# WizFi250_EVB_SCH_V100.net
KiCad netlist of a schematic drawn in EAGLE
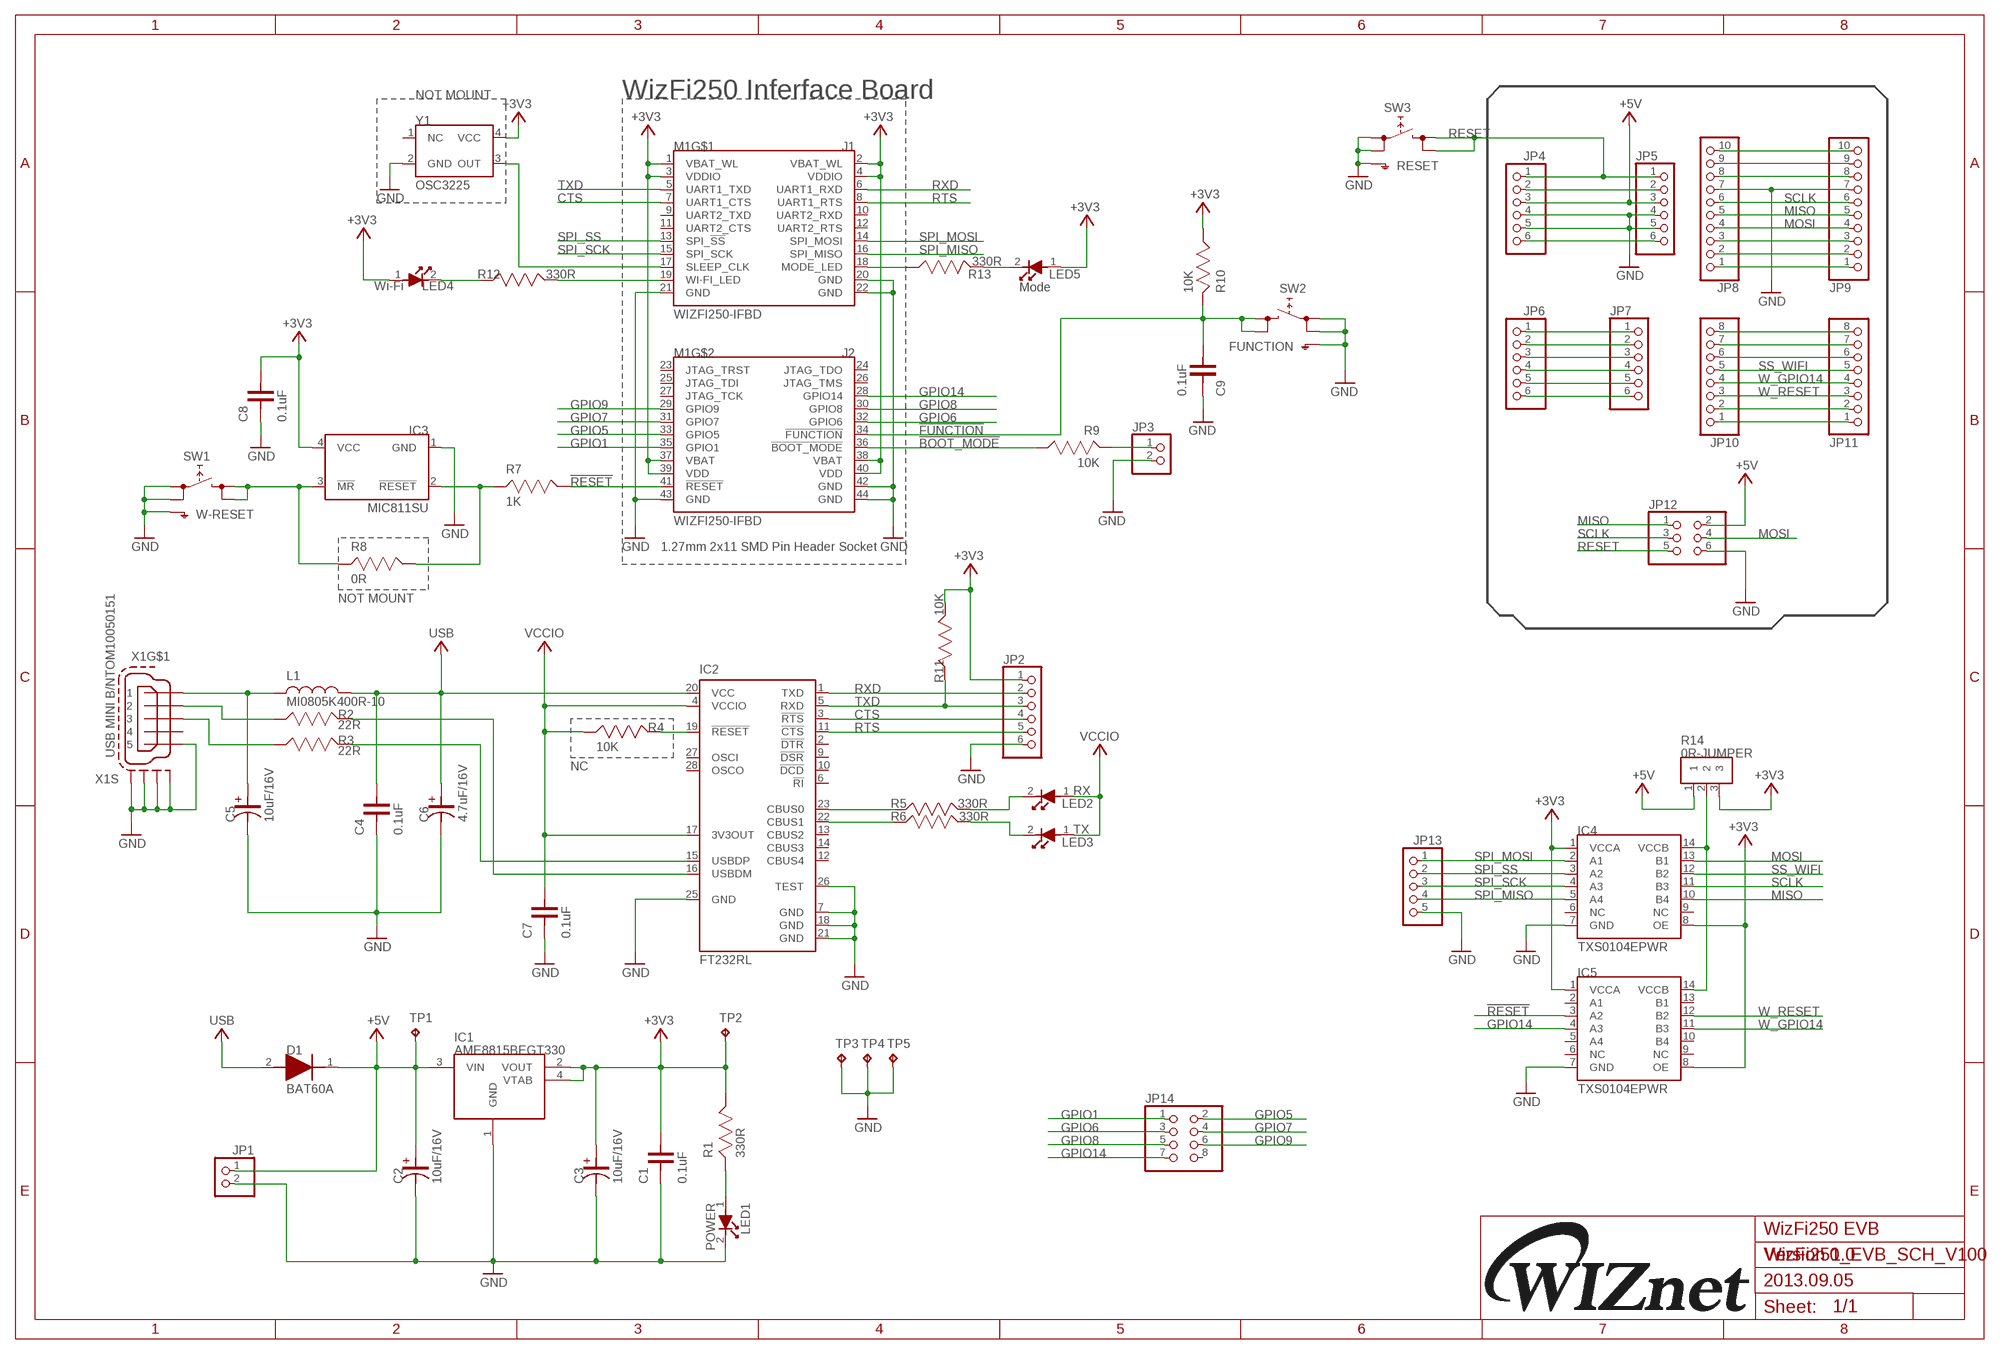
[diagram p0: schematic, sheet 1]

(export (version "E")
  (design (tool "Eeschema 10.0.6"))
  (components
    (comp (ref "C1")
      (value "0.1uF")
      (footprint "eagle-import:C-1608")
      (libsource (lib "eagle-import") (part "C-1608"))
    )
    (comp (ref "C2")
      (value "10uF/16V")
      (footprint "eagle-import:C-3216(TANTAL)")
      (libsource (lib "eagle-import") (part "C-3216(TANTAL)"))
    )
    (comp (ref "C3")
      (value "10uF/16V")
      (footprint "eagle-import:C-3216(TANTAL)")
      (libsource (lib "eagle-import") (part "C-3216(TANTAL)"))
    )
    (comp (ref "C4")
      (value "0.1uF")
      (footprint "eagle-import:C-1608")
      (libsource (lib "eagle-import") (part "C-1608"))
    )
    (comp (ref "C5")
      (value "10uF/16V")
      (footprint "eagle-import:C-3216(TANTAL)")
      (libsource (lib "eagle-import") (part "C-3216(TANTAL)"))
    )
    (comp (ref "C6")
      (value "4.7uF/16V")
      (footprint "eagle-import:C-3216(TANTAL)")
      (libsource (lib "eagle-import") (part "C-3216(TANTAL)"))
    )
    (comp (ref "C7")
      (value "0.1uF")
      (footprint "eagle-import:C-1608")
      (libsource (lib "eagle-import") (part "C-1608"))
    )
    (comp (ref "C8")
      (value "0.1uF")
      (footprint "eagle-import:C-1608")
      (libsource (lib "eagle-import") (part "C-1608"))
    )
    (comp (ref "C9")
      (value "0.1uF")
      (footprint "eagle-import:C-1608")
      (libsource (lib "eagle-import") (part "C-1608"))
    )
    (comp (ref "D1")
      (value "BAT60A")
      (footprint "eagle-import:BAT60A")
      (libsource (lib "eagle-import") (part "BAT60A"))
    )
    (comp (ref "IC1")
      (value "AME8815BEGT330")
      (footprint "eagle-import:SOT-223")
      (libsource (lib "eagle-import") (part "AME8815BEGT330"))
    )
    (comp (ref "IC2")
      (value "FT232RL")
      (footprint "eagle-import:SSOP28")
      (libsource (lib "eagle-import") (part "FT232RL"))
    )
    (comp (ref "IC3")
      (value "MIC811SU")
      (footprint "eagle-import:MIC811SU")
      (libsource (lib "eagle-import") (part "MIC811SU"))
    )
    (comp (ref "IC4")
      (value "TXS0104EPWR")
      (footprint "eagle-import:TXS0104EPWR")
      (libsource (lib "eagle-import") (part "TXS0104EPWR"))
    )
    (comp (ref "IC5")
      (value "TXS0104EPWR")
      (footprint "eagle-import:TXS0104EPWR")
      (libsource (lib "eagle-import") (part "TXS0104EPWR"))
    )
    (comp (ref "JP1")
      (value "PINHD-1X2")
      (footprint "eagle-import:1X02")
      (libsource (lib "eagle-import") (part "PINHD-1X2"))
    )
    (comp (ref "JP2")
      (value "PINHD-1X6")
      (footprint "eagle-import:1X06")
      (libsource (lib "eagle-import") (part "PINHD-1X6"))
    )
    (comp (ref "JP3")
      (value "PINHD-1X2")
      (footprint "eagle-import:1X02")
      (libsource (lib "eagle-import") (part "PINHD-1X2"))
    )
    (comp (ref "JP4")
      (value "PINHD-1X6")
      (footprint "eagle-import:1X06")
      (libsource (lib "eagle-import") (part "PINHD-1X6"))
    )
    (comp (ref "JP5")
      (value "PINHD-1X6")
      (footprint "eagle-import:1X06")
      (libsource (lib "eagle-import") (part "PINHD-1X6"))
    )
    (comp (ref "JP6")
      (value "PINHD-1X6")
      (footprint "eagle-import:1X06")
      (libsource (lib "eagle-import") (part "PINHD-1X6"))
    )
    (comp (ref "JP7")
      (value "PINHD-1X6")
      (footprint "eagle-import:1X06")
      (libsource (lib "eagle-import") (part "PINHD-1X6"))
    )
    (comp (ref "JP8")
      (value "PINHD-1X10")
      (footprint "eagle-import:1X10")
      (libsource (lib "eagle-import") (part "PINHD-1X10"))
    )
    (comp (ref "JP9")
      (value "PINHD-1X10")
      (footprint "eagle-import:1X10")
      (libsource (lib "eagle-import") (part "PINHD-1X10"))
    )
    (comp (ref "JP10")
      (value "PINHD-1X8")
      (footprint "eagle-import:1X08")
      (libsource (lib "eagle-import") (part "PINHD-1X8"))
    )
    (comp (ref "JP11")
      (value "PINHD-1X8")
      (footprint "eagle-import:1X08")
      (libsource (lib "eagle-import") (part "PINHD-1X8"))
    )
    (comp (ref "JP12")
      (value "PINHD-2X3")
      (footprint "eagle-import:2X03")
      (libsource (lib "eagle-import") (part "PINHD-2X3"))
    )
    (comp (ref "JP13")
      (value "PINHD-1X5")
      (footprint "eagle-import:1X05")
      (libsource (lib "eagle-import") (part "PINHD-1X5"))
    )
    (comp (ref "JP14")
      (value "PINHD-2X4")
      (footprint "eagle-import:2X04")
      (libsource (lib "eagle-import") (part "PINHD-2X4"))
    )
    (comp (ref "L1")
      (value "MI0805K400R-10")
      (footprint "eagle-import:L-2012")
      (libsource (lib "eagle-import") (part "L-2012"))
    )
    (comp (ref "LED1")
      (value "POWER")
      (footprint "eagle-import:LED-1608")
      (libsource (lib "eagle-import") (part "LED-1608"))
    )
    (comp (ref "LED2")
      (value "RX")
      (footprint "eagle-import:LED-1608")
      (libsource (lib "eagle-import") (part "LED-1608"))
    )
    (comp (ref "LED3")
      (value "TX")
      (footprint "eagle-import:LED-1608")
      (libsource (lib "eagle-import") (part "LED-1608"))
    )
    (comp (ref "LED4")
      (value "Wi-Fi")
      (footprint "eagle-import:LED-1608")
      (libsource (lib "eagle-import") (part "LED-1608"))
    )
    (comp (ref "LED5")
      (value "Mode")
      (footprint "eagle-import:LED-1608")
      (libsource (lib "eagle-import") (part "LED-1608"))
    )
    (comp (ref "M1")
      (value "WIZFI250-IFBD")
      (footprint "eagle-import:WIZFI250-IFBD")
      (libsource (lib "eagle-import") (part "WIZFI250-IFBD"))
    )
    (comp (ref "R1")
      (value "330R")
      (footprint "eagle-import:R-1608")
      (libsource (lib "eagle-import") (part "R-1608"))
    )
    (comp (ref "R2")
      (value "22R")
      (footprint "eagle-import:R-1608")
      (libsource (lib "eagle-import") (part "R-1608"))
    )
    (comp (ref "R3")
      (value "22R")
      (footprint "eagle-import:R-1608")
      (libsource (lib "eagle-import") (part "R-1608"))
    )
    (comp (ref "R4")
      (value "10K")
      (footprint "eagle-import:R-1608")
      (libsource (lib "eagle-import") (part "R-1608"))
    )
    (comp (ref "R5")
      (value "330R")
      (footprint "eagle-import:R-1608")
      (libsource (lib "eagle-import") (part "R-1608"))
    )
    (comp (ref "R6")
      (value "330R")
      (footprint "eagle-import:R-1608")
      (libsource (lib "eagle-import") (part "R-1608"))
    )
    (comp (ref "R7")
      (value "1K")
      (footprint "eagle-import:R-1608")
      (libsource (lib "eagle-import") (part "R-1608"))
    )
    (comp (ref "R8")
      (value "0R")
      (footprint "eagle-import:R-1608")
      (libsource (lib "eagle-import") (part "R-1608"))
    )
    (comp (ref "R9")
      (value "10K")
      (footprint "eagle-import:R-1608")
      (libsource (lib "eagle-import") (part "R-1608"))
    )
    (comp (ref "R10")
      (value "10K")
      (footprint "eagle-import:R-1608")
      (libsource (lib "eagle-import") (part "R-1608"))
    )
    (comp (ref "R11")
      (value "10K")
      (footprint "eagle-import:R-1608")
      (libsource (lib "eagle-import") (part "R-1608"))
    )
    (comp (ref "R12")
      (value "330R")
      (footprint "eagle-import:R-1608")
      (libsource (lib "eagle-import") (part "R-1608"))
    )
    (comp (ref "R13")
      (value "330R")
      (footprint "eagle-import:R-1608")
      (libsource (lib "eagle-import") (part "R-1608"))
    )
    (comp (ref "R14")
      (value "0R-JUMPER")
      (footprint "eagle-import:R-1608-JUMPER")
      (libsource (lib "eagle-import") (part "R-1608-JUMPER"))
    )
    (comp (ref "SW1")
      (value "W-RESET")
      (footprint "eagle-import:SKHMPXE010")
      (libsource (lib "eagle-import") (part "SKHMPE010S"))
    )
    (comp (ref "SW2")
      (value "FUNCTION")
      (footprint "eagle-import:SKHMPXE010")
      (libsource (lib "eagle-import") (part "SKHMPE010S"))
    )
    (comp (ref "SW3")
      (value "RESET")
      (footprint "eagle-import:SKHMPXE010")
      (libsource (lib "eagle-import") (part "SKHMPE010S"))
    )
    (comp (ref "TP1")
      (value "TPB1,27")
      (footprint "eagle-import:B1,27")
      (libsource (lib "eagle-import") (part "TPB1,27"))
    )
    (comp (ref "TP2")
      (value "TPB1,27")
      (footprint "eagle-import:B1,27")
      (libsource (lib "eagle-import") (part "TPB1,27"))
    )
    (comp (ref "TP3")
      (value "TPB1,27")
      (footprint "eagle-import:B1,27")
      (libsource (lib "eagle-import") (part "TPB1,27"))
    )
    (comp (ref "TP4")
      (value "TPB1,27")
      (footprint "eagle-import:B1,27")
      (libsource (lib "eagle-import") (part "TPB1,27"))
    )
    (comp (ref "TP5")
      (value "TPB1,27")
      (footprint "eagle-import:B1,27")
      (libsource (lib "eagle-import") (part "TPB1,27"))
    )
    (comp (ref "X1")
      (value "USB MINI B/NTOM10050151")
      (footprint "eagle-import:32005-201")
      (libsource (lib "eagle-import") (part "MINI-USB-SCHIELD-32005-201"))
    )
    (comp (ref "Y1")
      (value "OSC3225")
      (footprint "eagle-import:OSC3225")
      (libsource (lib "eagle-import") (part "OSC3225"))
    )
  )
  (nets
    (net (code "1") (name "+3V3") (class "Default")
      (node (ref "C1") (pin "2") (pinfunction "P$2_2") (pintype "passive"))
      (node (ref "C3") (pin "1") (pinfunction "P$1_1") (pintype "passive"))
      (node (ref "C8") (pin "2") (pinfunction "P$2_2") (pintype "passive"))
      (node (ref "IC1") (pin "2") (pinfunction "VOUT_2") (pintype "passive"))
      (node (ref "IC1") (pin "4") (pinfunction "VTAB_4") (pintype "passive"))
      (node (ref "IC3") (pin "4") (pinfunction "VCC_4") (pintype "passive"))
      (node (ref "IC4") (pin "1") (pinfunction "VCCA_1") (pintype "passive"))
      (node (ref "IC4") (pin "8") (pinfunction "OE_8") (pintype "passive"))
      (node (ref "IC5") (pin "1") (pinfunction "VCCA_1") (pintype "passive"))
      (node (ref "IC5") (pin "8") (pinfunction "OE_8") (pintype "passive"))
      (node (ref "JP2") (pin "1") (pinfunction "1_1") (pintype "passive"))
      (node (ref "LED4") (pin "1") (pinfunction "P$1_1") (pintype "bidirectional"))
      (node (ref "LED5") (pin "1") (pinfunction "P$1_1") (pintype "bidirectional"))
      (node (ref "M1") (pin "1") (pinfunction "VBAT_WL_1") (pintype "passive"))
      (node (ref "M1") (pin "2") (pinfunction "VBAT_WL_2") (pintype "passive"))
      (node (ref "M1") (pin "3") (pinfunction "VDDIO_3") (pintype "passive"))
      (node (ref "M1") (pin "37") (pinfunction "VBAT_37") (pintype "passive"))
      (node (ref "M1") (pin "38") (pinfunction "VBAT_38") (pintype "passive"))
      (node (ref "M1") (pin "39") (pinfunction "VDD_39") (pintype "passive"))
      (node (ref "M1") (pin "4") (pinfunction "VDDIO_4") (pintype "passive"))
      (node (ref "M1") (pin "40") (pinfunction "VDD_40") (pintype "passive"))
      (node (ref "R1") (pin "2") (pinfunction "P$2_2") (pintype "passive"))
      (node (ref "R10") (pin "2") (pinfunction "P$2_2") (pintype "passive"))
      (node (ref "R11") (pin "2") (pinfunction "P$2_2") (pintype "passive"))
      (node (ref "R14") (pin "3") (pinfunction "3_3") (pintype "passive"))
      (node (ref "TP2") (pin "TP") (pinfunction "TP_TP") (pintype "input"))
      (node (ref "Y1") (pin "4") (pinfunction "VCC_4") (pintype "passive"))
    )
    (net (code "2") (name "+5V") (class "Default")
      (node (ref "C2") (pin "1") (pinfunction "P$1_1") (pintype "passive"))
      (node (ref "D1") (pin "1") (pinfunction "1_1") (pintype "bidirectional"))
      (node (ref "IC1") (pin "3") (pinfunction "VIN_3") (pintype "passive"))
      (node (ref "JP1") (pin "1") (pinfunction "1_1") (pintype "passive"))
      (node (ref "JP12") (pin "2") (pinfunction "2_2") (pintype "passive"))
      (node (ref "JP4") (pin "3") (pinfunction "3_3") (pintype "passive"))
      (node (ref "JP5") (pin "3") (pinfunction "3_3") (pintype "passive"))
      (node (ref "R14") (pin "1") (pinfunction "1_1") (pintype "passive"))
      (node (ref "TP1") (pin "TP") (pinfunction "TP_TP") (pintype "input"))
    )
    (net (code "3") (name "/CTS") (class "Default")
      (node (ref "IC2") (pin "3") (pinfunction "~{RTS}_3") (pintype "output"))
      (node (ref "JP2") (pin "4") (pinfunction "4_4") (pintype "passive"))
      (node (ref "M1") (pin "7") (pinfunction "UART1_CTS_7") (pintype "passive"))
    )
    (net (code "4") (name "/GPIO1") (class "Default")
      (node (ref "JP14") (pin "1") (pinfunction "1_1") (pintype "passive"))
      (node (ref "M1") (pin "35") (pinfunction "GPIO1_35") (pintype "passive"))
    )
    (net (code "5") (name "/GPIO5") (class "Default")
      (node (ref "JP14") (pin "2") (pinfunction "2_2") (pintype "passive"))
      (node (ref "M1") (pin "33") (pinfunction "GPIO5_33") (pintype "passive"))
    )
    (net (code "6") (name "/GPIO6") (class "Default")
      (node (ref "JP14") (pin "3") (pinfunction "3_3") (pintype "passive"))
      (node (ref "M1") (pin "32") (pinfunction "GPIO6_32") (pintype "passive"))
    )
    (net (code "7") (name "/GPIO7") (class "Default")
      (node (ref "JP14") (pin "4") (pinfunction "4_4") (pintype "passive"))
      (node (ref "M1") (pin "31") (pinfunction "GPIO7_31") (pintype "passive"))
    )
    (net (code "8") (name "/GPIO8") (class "Default")
      (node (ref "JP14") (pin "5") (pinfunction "5_5") (pintype "passive"))
      (node (ref "M1") (pin "30") (pinfunction "GPIO8_30") (pintype "passive"))
    )
    (net (code "9") (name "/GPIO9") (class "Default")
      (node (ref "JP14") (pin "6") (pinfunction "6_6") (pintype "passive"))
      (node (ref "M1") (pin "29") (pinfunction "GPIO9_29") (pintype "passive"))
    )
    (net (code "10") (name "/GPIO14") (class "Default")
      (node (ref "IC5") (pin "4") (pinfunction "A3_4") (pintype "passive"))
      (node (ref "JP14") (pin "7") (pinfunction "7_7") (pintype "passive"))
      (node (ref "M1") (pin "28") (pinfunction "GPIO14_28") (pintype "passive"))
    )
    (net (code "11") (name "/MISO") (class "Default")
      (node (ref "IC4") (pin "10") (pinfunction "B4_10") (pintype "passive"))
      (node (ref "JP12") (pin "1") (pinfunction "1_1") (pintype "passive"))
      (node (ref "JP8") (pin "5") (pinfunction "5_5") (pintype "passive"))
      (node (ref "JP9") (pin "5") (pinfunction "5_5") (pintype "passive"))
    )
    (net (code "12") (name "/MOSI") (class "Default")
      (node (ref "IC4") (pin "13") (pinfunction "B1_13") (pintype "passive"))
      (node (ref "JP12") (pin "4") (pinfunction "4_4") (pintype "passive"))
      (node (ref "JP8") (pin "4") (pinfunction "4_4") (pintype "passive"))
      (node (ref "JP9") (pin "4") (pinfunction "4_4") (pintype "passive"))
    )
    (net (code "13") (name "/RESET") (class "Default")
      (node (ref "JP12") (pin "5") (pinfunction "5_5") (pintype "passive"))
      (node (ref "JP4") (pin "1") (pinfunction "1_1") (pintype "passive"))
      (node (ref "JP5") (pin "1") (pinfunction "1_1") (pintype "passive"))
      (node (ref "SW3") (pin "3") (pinfunction "2.1_3") (pintype "passive"))
      (node (ref "SW3") (pin "4") (pinfunction "2.2_4") (pintype "passive"))
    )
    (net (code "14") (name "/RTS") (class "Default")
      (node (ref "IC2") (pin "11") (pinfunction "~{CTS}_11") (pintype "input"))
      (node (ref "JP2") (pin "5") (pinfunction "5_5") (pintype "passive"))
      (node (ref "M1") (pin "8") (pinfunction "UART1_RTS_8") (pintype "passive"))
    )
    (net (code "15") (name "/RXD") (class "Default")
      (node (ref "IC2") (pin "1") (pinfunction "TXD_1") (pintype "output"))
      (node (ref "JP2") (pin "2") (pinfunction "2_2") (pintype "passive"))
      (node (ref "M1") (pin "6") (pinfunction "UART1_RXD_6") (pintype "passive"))
    )
    (net (code "16") (name "/SCLK") (class "Default")
      (node (ref "IC4") (pin "11") (pinfunction "B3_11") (pintype "passive"))
      (node (ref "JP12") (pin "3") (pinfunction "3_3") (pintype "passive"))
      (node (ref "JP8") (pin "6") (pinfunction "6_6") (pintype "passive"))
      (node (ref "JP9") (pin "6") (pinfunction "6_6") (pintype "passive"))
    )
    (net (code "17") (name "/SPI_MISO") (class "Default")
      (node (ref "IC4") (pin "5") (pinfunction "A4_5") (pintype "passive"))
      (node (ref "JP13") (pin "4") (pinfunction "4_4") (pintype "passive"))
      (node (ref "M1") (pin "16") (pinfunction "SPI_MISO_16") (pintype "passive"))
    )
    (net (code "18") (name "/SPI_MOSI") (class "Default")
      (node (ref "IC4") (pin "2") (pinfunction "A1_2") (pintype "passive"))
      (node (ref "JP13") (pin "1") (pinfunction "1_1") (pintype "passive"))
      (node (ref "M1") (pin "14") (pinfunction "SPI_MOSI_14") (pintype "passive"))
    )
    (net (code "19") (name "/SPI_SCK") (class "Default")
      (node (ref "IC4") (pin "4") (pinfunction "A3_4") (pintype "passive"))
      (node (ref "JP13") (pin "3") (pinfunction "3_3") (pintype "passive"))
      (node (ref "M1") (pin "15") (pinfunction "SPI_SCK_15") (pintype "passive"))
    )
    (net (code "20") (name "/SPI_SS") (class "Default")
      (node (ref "IC4") (pin "3") (pinfunction "A2_3") (pintype "passive"))
      (node (ref "JP13") (pin "2") (pinfunction "2_2") (pintype "passive"))
      (node (ref "M1") (pin "13") (pinfunction "SPI_~{SS}_13") (pintype "passive"))
    )
    (net (code "21") (name "/SS_WIFI") (class "Default")
      (node (ref "IC4") (pin "12") (pinfunction "B2_12") (pintype "passive"))
      (node (ref "JP10") (pin "5") (pinfunction "5_5") (pintype "passive"))
      (node (ref "JP11") (pin "5") (pinfunction "5_5") (pintype "passive"))
    )
    (net (code "22") (name "/TXD") (class "Default")
      (node (ref "IC2") (pin "5") (pinfunction "RXD_5") (pintype "input"))
      (node (ref "JP2") (pin "3") (pinfunction "3_3") (pintype "passive"))
      (node (ref "M1") (pin "5") (pinfunction "UART1_TXD_5") (pintype "passive"))
      (node (ref "R11") (pin "1") (pinfunction "P$1_1") (pintype "passive"))
    )
    (net (code "23") (name "/W_GPIO14") (class "Default")
      (node (ref "IC5") (pin "11") (pinfunction "B3_11") (pintype "passive"))
      (node (ref "JP10") (pin "4") (pinfunction "4_4") (pintype "passive"))
      (node (ref "JP11") (pin "4") (pinfunction "4_4") (pintype "passive"))
    )
    (net (code "24") (name "/W_RESET") (class "Default")
      (node (ref "IC5") (pin "12") (pinfunction "B2_12") (pintype "passive"))
      (node (ref "JP10") (pin "3") (pinfunction "3_3") (pintype "passive"))
      (node (ref "JP11") (pin "3") (pinfunction "3_3") (pintype "passive"))
    )
    (net (code "25") (name "/~{BOOT_MODE}") (class "Default")
      (node (ref "M1") (pin "36") (pinfunction "~{BOOT_MODE}_36") (pintype "passive"))
      (node (ref "R9") (pin "2") (pinfunction "P$2_2") (pintype "passive"))
    )
    (net (code "26") (name "/~{FUNCTION}") (class "Default")
      (node (ref "C9") (pin "2") (pinfunction "P$2_2") (pintype "passive"))
      (node (ref "M1") (pin "34") (pinfunction "~{FUNCTION}_34") (pintype "passive"))
      (node (ref "R10") (pin "1") (pinfunction "P$1_1") (pintype "passive"))
      (node (ref "SW2") (pin "3") (pinfunction "2.1_3") (pintype "passive"))
      (node (ref "SW2") (pin "4") (pinfunction "2.2_4") (pintype "passive"))
    )
    (net (code "27") (name "/~{RESET}") (class "Default")
      (node (ref "IC5") (pin "3") (pinfunction "A2_3") (pintype "passive"))
      (node (ref "M1") (pin "41") (pinfunction "~{RESET}_41") (pintype "passive"))
      (node (ref "R7") (pin "2") (pinfunction "P$2_2") (pintype "passive"))
    )
    (net (code "28") (name "GND") (class "Default")
      (node (ref "C1") (pin "1") (pinfunction "P$1_1") (pintype "passive"))
      (node (ref "C2") (pin "2") (pinfunction "P$2_2") (pintype "passive"))
      (node (ref "C3") (pin "2") (pinfunction "P$2_2") (pintype "passive"))
      (node (ref "C4") (pin "1") (pinfunction "P$1_1") (pintype "passive"))
      (node (ref "C5") (pin "2") (pinfunction "P$2_2") (pintype "passive"))
      (node (ref "C6") (pin "2") (pinfunction "P$2_2") (pintype "passive"))
      (node (ref "C7") (pin "1") (pinfunction "P$1_1") (pintype "passive"))
      (node (ref "C8") (pin "1") (pinfunction "P$1_1") (pintype "passive"))
      (node (ref "C9") (pin "1") (pinfunction "P$1_1") (pintype "passive"))
      (node (ref "IC1") (pin "1") (pinfunction "GND_1") (pintype "passive"))
      (node (ref "IC2") (pin "18") (pinfunction "GND_18") (pintype "power_in"))
      (node (ref "IC2") (pin "21") (pinfunction "GND_21") (pintype "power_in"))
      (node (ref "IC2") (pin "25") (pinfunction "GND_25") (pintype "power_in"))
      (node (ref "IC2") (pin "26") (pinfunction "TEST_26") (pintype "input"))
      (node (ref "IC2") (pin "7") (pinfunction "GND_7") (pintype "power_in"))
      (node (ref "IC3") (pin "1") (pinfunction "GND_1") (pintype "passive"))
      (node (ref "IC4") (pin "7") (pinfunction "GND_7") (pintype "passive"))
      (node (ref "IC5") (pin "7") (pinfunction "GND_7") (pintype "passive"))
      (node (ref "JP1") (pin "2") (pinfunction "2_2") (pintype "passive"))
      (node (ref "JP12") (pin "6") (pinfunction "6_6") (pintype "passive"))
      (node (ref "JP13") (pin "5") (pinfunction "5_5") (pintype "passive"))
      (node (ref "JP2") (pin "6") (pinfunction "6_6") (pintype "passive"))
      (node (ref "JP3") (pin "2") (pinfunction "2_2") (pintype "passive"))
      (node (ref "JP4") (pin "4") (pinfunction "4_4") (pintype "passive"))
      (node (ref "JP4") (pin "5") (pinfunction "5_5") (pintype "passive"))
      (node (ref "JP5") (pin "4") (pinfunction "4_4") (pintype "passive"))
      (node (ref "JP5") (pin "5") (pinfunction "5_5") (pintype "passive"))
      (node (ref "JP8") (pin "7") (pinfunction "7_7") (pintype "passive"))
      (node (ref "JP9") (pin "7") (pinfunction "7_7") (pintype "passive"))
      (node (ref "LED1") (pin "2") (pinfunction "P$2_2") (pintype "bidirectional"))
      (node (ref "M1") (pin "20") (pinfunction "GND_20") (pintype "passive"))
      (node (ref "M1") (pin "21") (pinfunction "GND_21") (pintype "passive"))
      (node (ref "M1") (pin "22") (pinfunction "GND_22") (pintype "passive"))
      (node (ref "M1") (pin "42") (pinfunction "GND_42") (pintype "passive"))
      (node (ref "M1") (pin "43") (pinfunction "GND_43") (pintype "passive"))
      (node (ref "M1") (pin "44") (pinfunction "GND_44") (pintype "passive"))
      (node (ref "SW1") (pin "1") (pinfunction "1.1_1") (pintype "passive"))
      (node (ref "SW1") (pin "2") (pinfunction "1.2_2") (pintype "passive"))
      (node (ref "SW1") (pin "5") (pinfunction "SH_5") (pintype "passive"))
      (node (ref "SW2") (pin "1") (pinfunction "1.1_1") (pintype "passive"))
      (node (ref "SW2") (pin "2") (pinfunction "1.2_2") (pintype "passive"))
      (node (ref "SW2") (pin "5") (pinfunction "SH_5") (pintype "passive"))
      (node (ref "SW3") (pin "1") (pinfunction "1.1_1") (pintype "passive"))
      (node (ref "SW3") (pin "2") (pinfunction "1.2_2") (pintype "passive"))
      (node (ref "SW3") (pin "5") (pinfunction "SH_5") (pintype "passive"))
      (node (ref "TP3") (pin "TP") (pinfunction "TP_TP") (pintype "input"))
      (node (ref "TP4") (pin "TP") (pinfunction "TP_TP") (pintype "input"))
      (node (ref "TP5") (pin "TP") (pinfunction "TP_TP") (pintype "input"))
      (node (ref "X1") (pin "5") (pinfunction "5_5") (pintype "passive"))
      (node (ref "X1") (pin "M1") (pinfunction "S1_M1") (pintype "passive"))
      (node (ref "X1") (pin "M2") (pinfunction "S2_M2") (pintype "passive"))
      (node (ref "X1") (pin "M3") (pinfunction "S3_M3") (pintype "passive"))
      (node (ref "X1") (pin "M4") (pinfunction "S4_M4") (pintype "passive"))
      (node (ref "Y1") (pin "2") (pinfunction "GND_2") (pintype "passive"))
    )
    (net (code "29") (name "Net-(C5-P$1)") (class "Default")
      (node (ref "C5") (pin "1") (pinfunction "P$1_1") (pintype "passive"))
      (node (ref "L1") (pin "1") (pinfunction "1_1") (pintype "passive"))
      (node (ref "X1") (pin "1") (pinfunction "1_1") (pintype "passive"))
    )
    (net (code "30") (name "Net-(IC2-CBUS0)") (class "Default")
      (node (ref "IC2") (pin "23") (pinfunction "CBUS0_23") (pintype "bidirectional"))
      (node (ref "R5") (pin "1") (pinfunction "P$1_1") (pintype "passive"))
    )
    (net (code "31") (name "Net-(IC2-CBUS1)") (class "Default")
      (node (ref "IC2") (pin "22") (pinfunction "CBUS1_22") (pintype "bidirectional"))
      (node (ref "R6") (pin "1") (pinfunction "P$1_1") (pintype "passive"))
    )
    (net (code "32") (name "Net-(IC2-USBDM)") (class "Default")
      (node (ref "IC2") (pin "16") (pinfunction "USBDM_16") (pintype "bidirectional"))
      (node (ref "R2") (pin "2") (pinfunction "P$2_2") (pintype "passive"))
    )
    (net (code "33") (name "Net-(IC2-USBDP)") (class "Default")
      (node (ref "IC2") (pin "15") (pinfunction "USBDP_15") (pintype "bidirectional"))
      (node (ref "R3") (pin "2") (pinfunction "P$2_2") (pintype "passive"))
    )
    (net (code "34") (name "Net-(IC2-~{RESET})") (class "Default")
      (node (ref "IC2") (pin "19") (pinfunction "~{RESET}_19") (pintype "input"))
      (node (ref "R4") (pin "2") (pinfunction "P$2_2") (pintype "passive"))
    )
    (net (code "35") (name "Net-(IC3-~{MR})") (class "Default")
      (node (ref "IC3") (pin "3") (pinfunction "~{MR}_3") (pintype "passive"))
      (node (ref "R8") (pin "1") (pinfunction "P$1_1") (pintype "passive"))
      (node (ref "SW1") (pin "3") (pinfunction "2.1_3") (pintype "passive"))
      (node (ref "SW1") (pin "4") (pinfunction "2.2_4") (pintype "passive"))
    )
    (net (code "36") (name "Net-(IC3-~{RESET})") (class "Default")
      (node (ref "IC3") (pin "2") (pinfunction "~{RESET}_2") (pintype "passive"))
      (node (ref "R7") (pin "1") (pinfunction "P$1_1") (pintype "passive"))
      (node (ref "R8") (pin "2") (pinfunction "P$2_2") (pintype "passive"))
    )
    (net (code "37") (name "Net-(IC4-VCCB)") (class "Default")
      (node (ref "IC4") (pin "14") (pinfunction "VCCB_14") (pintype "passive"))
      (node (ref "IC5") (pin "14") (pinfunction "VCCB_14") (pintype "passive"))
      (node (ref "R14") (pin "2") (pinfunction "2_2") (pintype "passive"))
    )
    (net (code "38") (name "Net-(JP4-Pad2)") (class "Default")
      (node (ref "JP4") (pin "2") (pinfunction "2_2") (pintype "passive"))
      (node (ref "JP5") (pin "2") (pinfunction "2_2") (pintype "passive"))
    )
    (net (code "39") (name "Net-(JP4-Pad6)") (class "Default")
      (node (ref "JP4") (pin "6") (pinfunction "6_6") (pintype "passive"))
      (node (ref "JP5") (pin "6") (pinfunction "6_6") (pintype "passive"))
    )
    (net (code "40") (name "Net-(JP6-Pad1)") (class "Default")
      (node (ref "JP6") (pin "1") (pinfunction "1_1") (pintype "passive"))
      (node (ref "JP7") (pin "1") (pinfunction "1_1") (pintype "passive"))
    )
    (net (code "41") (name "Net-(JP6-Pad2)") (class "Default")
      (node (ref "JP6") (pin "2") (pinfunction "2_2") (pintype "passive"))
      (node (ref "JP7") (pin "2") (pinfunction "2_2") (pintype "passive"))
    )
    (net (code "42") (name "Net-(JP6-Pad3)") (class "Default")
      (node (ref "JP6") (pin "3") (pinfunction "3_3") (pintype "passive"))
      (node (ref "JP7") (pin "3") (pinfunction "3_3") (pintype "passive"))
    )
    (net (code "43") (name "Net-(JP6-Pad4)") (class "Default")
      (node (ref "JP6") (pin "4") (pinfunction "4_4") (pintype "passive"))
      (node (ref "JP7") (pin "4") (pinfunction "4_4") (pintype "passive"))
    )
    (net (code "44") (name "Net-(JP6-Pad5)") (class "Default")
      (node (ref "JP6") (pin "5") (pinfunction "5_5") (pintype "passive"))
      (node (ref "JP7") (pin "5") (pinfunction "5_5") (pintype "passive"))
    )
    (net (code "45") (name "Net-(JP6-Pad6)") (class "Default")
      (node (ref "JP6") (pin "6") (pinfunction "6_6") (pintype "passive"))
      (node (ref "JP7") (pin "6") (pinfunction "6_6") (pintype "passive"))
    )
    (net (code "46") (name "Net-(JP8-Pad1)") (class "Default")
      (node (ref "JP8") (pin "1") (pinfunction "1_1") (pintype "passive"))
      (node (ref "JP9") (pin "1") (pinfunction "1_1") (pintype "passive"))
    )
    (net (code "47") (name "Net-(JP8-Pad2)") (class "Default")
      (node (ref "JP8") (pin "2") (pinfunction "2_2") (pintype "passive"))
      (node (ref "JP9") (pin "2") (pinfunction "2_2") (pintype "passive"))
    )
    (net (code "48") (name "Net-(JP8-Pad3)") (class "Default")
      (node (ref "JP8") (pin "3") (pinfunction "3_3") (pintype "passive"))
      (node (ref "JP9") (pin "3") (pinfunction "3_3") (pintype "passive"))
    )
    (net (code "49") (name "Net-(JP8-Pad8)") (class "Default")
      (node (ref "JP8") (pin "8") (pinfunction "8_8") (pintype "passive"))
      (node (ref "JP9") (pin "8") (pinfunction "8_8") (pintype "passive"))
    )
    (net (code "50") (name "Net-(JP8-Pad9)") (class "Default")
      (node (ref "JP8") (pin "9") (pinfunction "9_9") (pintype "passive"))
      (node (ref "JP9") (pin "9") (pinfunction "9_9") (pintype "passive"))
    )
    (net (code "51") (name "Net-(JP8-Pad10)") (class "Default")
      (node (ref "JP8") (pin "10") (pinfunction "10_10") (pintype "passive"))
      (node (ref "JP9") (pin "10") (pinfunction "10_10") (pintype "passive"))
    )
    (net (code "52") (name "Net-(JP10-Pad1)") (class "Default")
      (node (ref "JP10") (pin "1") (pinfunction "1_1") (pintype "passive"))
      (node (ref "JP11") (pin "1") (pinfunction "1_1") (pintype "passive"))
    )
    (net (code "53") (name "Net-(JP10-Pad2)") (class "Default")
      (node (ref "JP10") (pin "2") (pinfunction "2_2") (pintype "passive"))
      (node (ref "JP11") (pin "2") (pinfunction "2_2") (pintype "passive"))
    )
    (net (code "54") (name "Net-(JP10-Pad6)") (class "Default")
      (node (ref "JP10") (pin "6") (pinfunction "6_6") (pintype "passive"))
      (node (ref "JP11") (pin "6") (pinfunction "6_6") (pintype "passive"))
    )
    (net (code "55") (name "Net-(JP10-Pad7)") (class "Default")
      (node (ref "JP10") (pin "7") (pinfunction "7_7") (pintype "passive"))
      (node (ref "JP11") (pin "7") (pinfunction "7_7") (pintype "passive"))
    )
    (net (code "56") (name "Net-(JP10-Pad8)") (class "Default")
      (node (ref "JP10") (pin "8") (pinfunction "8_8") (pintype "passive"))
      (node (ref "JP11") (pin "8") (pinfunction "8_8") (pintype "passive"))
    )
    (net (code "57") (name "Net-(LED1-P$1)") (class "Default")
      (node (ref "LED1") (pin "1") (pinfunction "P$1_1") (pintype "bidirectional"))
      (node (ref "R1") (pin "1") (pinfunction "P$1_1") (pintype "passive"))
    )
    (net (code "58") (name "Net-(LED2-P$2)") (class "Default")
      (node (ref "LED2") (pin "2") (pinfunction "P$2_2") (pintype "bidirectional"))
      (node (ref "R5") (pin "2") (pinfunction "P$2_2") (pintype "passive"))
    )
    (net (code "59") (name "Net-(LED3-P$2)") (class "Default")
      (node (ref "LED3") (pin "2") (pinfunction "P$2_2") (pintype "bidirectional"))
      (node (ref "R6") (pin "2") (pinfunction "P$2_2") (pintype "passive"))
    )
    (net (code "60") (name "Net-(LED4-P$2)") (class "Default")
      (node (ref "LED4") (pin "2") (pinfunction "P$2_2") (pintype "bidirectional"))
      (node (ref "R12") (pin "1") (pinfunction "P$1_1") (pintype "passive"))
    )
    (net (code "61") (name "Net-(LED5-P$2)") (class "Default")
      (node (ref "LED5") (pin "2") (pinfunction "P$2_2") (pintype "bidirectional"))
      (node (ref "R13") (pin "2") (pinfunction "P$2_2") (pintype "passive"))
    )
    (net (code "62") (name "Net-(M1A-MODE_LED)") (class "Default")
      (node (ref "M1") (pin "18") (pinfunction "MODE_LED_18") (pintype "passive"))
      (node (ref "R13") (pin "1") (pinfunction "P$1_1") (pintype "passive"))
    )
    (net (code "63") (name "Net-(M1A-SLEEP_CLK)") (class "Default")
      (node (ref "M1") (pin "17") (pinfunction "SLEEP_CLK_17") (pintype "passive"))
      (node (ref "Y1") (pin "3") (pinfunction "OUT_3") (pintype "passive"))
    )
    (net (code "64") (name "Net-(M1A-WI-FI_LED)") (class "Default")
      (node (ref "M1") (pin "19") (pinfunction "WI-FI_LED_19") (pintype "passive"))
      (node (ref "R12") (pin "2") (pinfunction "P$2_2") (pintype "passive"))
    )
    (net (code "65") (name "Net-(R2-P$1)") (class "Default")
      (node (ref "R2") (pin "1") (pinfunction "P$1_1") (pintype "passive"))
      (node (ref "X1") (pin "2") (pinfunction "2_2") (pintype "passive"))
    )
    (net (code "66") (name "Net-(R3-P$1)") (class "Default")
      (node (ref "R3") (pin "1") (pinfunction "P$1_1") (pintype "passive"))
      (node (ref "X1") (pin "3") (pinfunction "3_3") (pintype "passive"))
    )
    (net (code "67") (name "Net-(R9-P$1)") (class "Default")
      (node (ref "JP3") (pin "1") (pinfunction "1_1") (pintype "passive"))
      (node (ref "R9") (pin "1") (pinfunction "P$1_1") (pintype "passive"))
    )
    (net (code "68") (name "USB") (class "Default")
      (node (ref "C4") (pin "2") (pinfunction "P$2_2") (pintype "passive"))
      (node (ref "C6") (pin "1") (pinfunction "P$1_1") (pintype "passive"))
      (node (ref "D1") (pin "2") (pinfunction "2_2") (pintype "bidirectional"))
      (node (ref "IC2") (pin "20") (pinfunction "VCC_20") (pintype "power_in"))
      (node (ref "L1") (pin "2") (pinfunction "2_2") (pintype "passive"))
    )
    (net (code "69") (name "VCCIO") (class "Default")
      (node (ref "C7") (pin "2") (pinfunction "P$2_2") (pintype "passive"))
      (node (ref "IC2") (pin "17") (pinfunction "3V3OUT_17") (pintype "output"))
      (node (ref "IC2") (pin "4") (pinfunction "VCCIO_4") (pintype "power_in"))
      (node (ref "LED2") (pin "1") (pinfunction "P$1_1") (pintype "bidirectional"))
      (node (ref "LED3") (pin "1") (pinfunction "P$1_1") (pintype "bidirectional"))
      (node (ref "R4") (pin "1") (pinfunction "P$1_1") (pintype "passive"))
    )
    (net (code "70") (name "unconnected-(IC2-CBUS2-Pad13)") (class "Default")
      (node (ref "IC2") (pin "13") (pinfunction "CBUS2_13") (pintype "bidirectional"))
    )
    (net (code "71") (name "unconnected-(IC2-CBUS3-Pad14)") (class "Default")
      (node (ref "IC2") (pin "14") (pinfunction "CBUS3_14") (pintype "bidirectional"))
    )
    (net (code "72") (name "unconnected-(IC2-CBUS4-Pad12)") (class "Default")
      (node (ref "IC2") (pin "12") (pinfunction "CBUS4_12") (pintype "bidirectional"))
    )
    (net (code "73") (name "unconnected-(IC2-OSCI-Pad27)") (class "Default")
      (node (ref "IC2") (pin "27") (pinfunction "OSCI_27") (pintype "input"))
    )
    (net (code "74") (name "unconnected-(IC2-OSCO-Pad28)") (class "Default")
      (node (ref "IC2") (pin "28") (pinfunction "OSCO_28") (pintype "output"))
    )
    (net (code "75") (name "unconnected-(IC2-~{DCD}-Pad10)") (class "Default")
      (node (ref "IC2") (pin "10") (pinfunction "~{DCD}_10") (pintype "input"))
    )
    (net (code "76") (name "unconnected-(IC2-~{DSR}-Pad9)") (class "Default")
      (node (ref "IC2") (pin "9") (pinfunction "~{DSR}_9") (pintype "input"))
    )
    (net (code "77") (name "unconnected-(IC2-~{DTR}-Pad2)") (class "Default")
      (node (ref "IC2") (pin "2") (pinfunction "~{DTR}_2") (pintype "output"))
    )
    (net (code "78") (name "unconnected-(IC2-~{RI}-Pad6)") (class "Default")
      (node (ref "IC2") (pin "6") (pinfunction "~{RI}_6") (pintype "input"))
    )
    (net (code "79") (name "unconnected-(IC4-NC-Pad6)") (class "Default")
      (node (ref "IC4") (pin "6") (pinfunction "NC_6") (pintype "passive"))
    )
    (net (code "80") (name "unconnected-(IC4-NC-Pad9)") (class "Default")
      (node (ref "IC4") (pin "9") (pinfunction "NC_9") (pintype "passive"))
    )
    (net (code "81") (name "unconnected-(IC5-A1-Pad2)") (class "Default")
      (node (ref "IC5") (pin "2") (pinfunction "A1_2") (pintype "passive"))
    )
    (net (code "82") (name "unconnected-(IC5-A4-Pad5)") (class "Default")
      (node (ref "IC5") (pin "5") (pinfunction "A4_5") (pintype "passive"))
    )
    (net (code "83") (name "unconnected-(IC5-B1-Pad13)") (class "Default")
      (node (ref "IC5") (pin "13") (pinfunction "B1_13") (pintype "passive"))
    )
    (net (code "84") (name "unconnected-(IC5-B4-Pad10)") (class "Default")
      (node (ref "IC5") (pin "10") (pinfunction "B4_10") (pintype "passive"))
    )
    (net (code "85") (name "unconnected-(IC5-NC-Pad6)") (class "Default")
      (node (ref "IC5") (pin "6") (pinfunction "NC_6") (pintype "passive"))
    )
    (net (code "86") (name "unconnected-(IC5-NC-Pad9)") (class "Default")
      (node (ref "IC5") (pin "9") (pinfunction "NC_9") (pintype "passive"))
    )
    (net (code "87") (name "unconnected-(JP14-Pad8)") (class "Default")
      (node (ref "JP14") (pin "8") (pinfunction "8_8") (pintype "passive"))
    )
    (net (code "88") (name "unconnected-(M1A-UART2_CTS-Pad11)") (class "Default")
      (node (ref "M1") (pin "11") (pinfunction "UART2_CTS_11") (pintype "passive"))
    )
    (net (code "89") (name "unconnected-(M1A-UART2_RTS-Pad12)") (class "Default")
      (node (ref "M1") (pin "12") (pinfunction "UART2_RTS_12") (pintype "passive"))
    )
    (net (code "90") (name "unconnected-(M1A-UART2_RXD-Pad10)") (class "Default")
      (node (ref "M1") (pin "10") (pinfunction "UART2_RXD_10") (pintype "passive"))
    )
    (net (code "91") (name "unconnected-(M1A-UART2_TXD-Pad9)") (class "Default")
      (node (ref "M1") (pin "9") (pinfunction "UART2_TXD_9") (pintype "passive"))
    )
    (net (code "92") (name "unconnected-(M1B-JTAG_TCK-Pad27)") (class "Default")
      (node (ref "M1") (pin "27") (pinfunction "JTAG_TCK_27") (pintype "passive"))
    )
    (net (code "93") (name "unconnected-(M1B-JTAG_TDI-Pad25)") (class "Default")
      (node (ref "M1") (pin "25") (pinfunction "JTAG_TDI_25") (pintype "passive"))
    )
    (net (code "94") (name "unconnected-(M1B-JTAG_TDO-Pad24)") (class "Default")
      (node (ref "M1") (pin "24") (pinfunction "JTAG_TDO_24") (pintype "passive"))
    )
    (net (code "95") (name "unconnected-(M1B-JTAG_TMS-Pad26)") (class "Default")
      (node (ref "M1") (pin "26") (pinfunction "JTAG_TMS_26") (pintype "passive"))
    )
    (net (code "96") (name "unconnected-(M1B-JTAG_TRST-Pad23)") (class "Default")
      (node (ref "M1") (pin "23") (pinfunction "JTAG_TRST_23") (pintype "passive"))
    )
    (net (code "97") (name "unconnected-(X1-Pad4)") (class "Default")
      (node (ref "X1") (pin "4") (pinfunction "4_4") (pintype "passive"))
    )
    (net (code "98") (name "unconnected-(Y1-NC-Pad1)") (class "Default")
      (node (ref "Y1") (pin "1") (pinfunction "NC_1") (pintype "passive"))
    )
  )
)
